# 3.net
KiCad netlist of a schematic drawn in Altium Designer
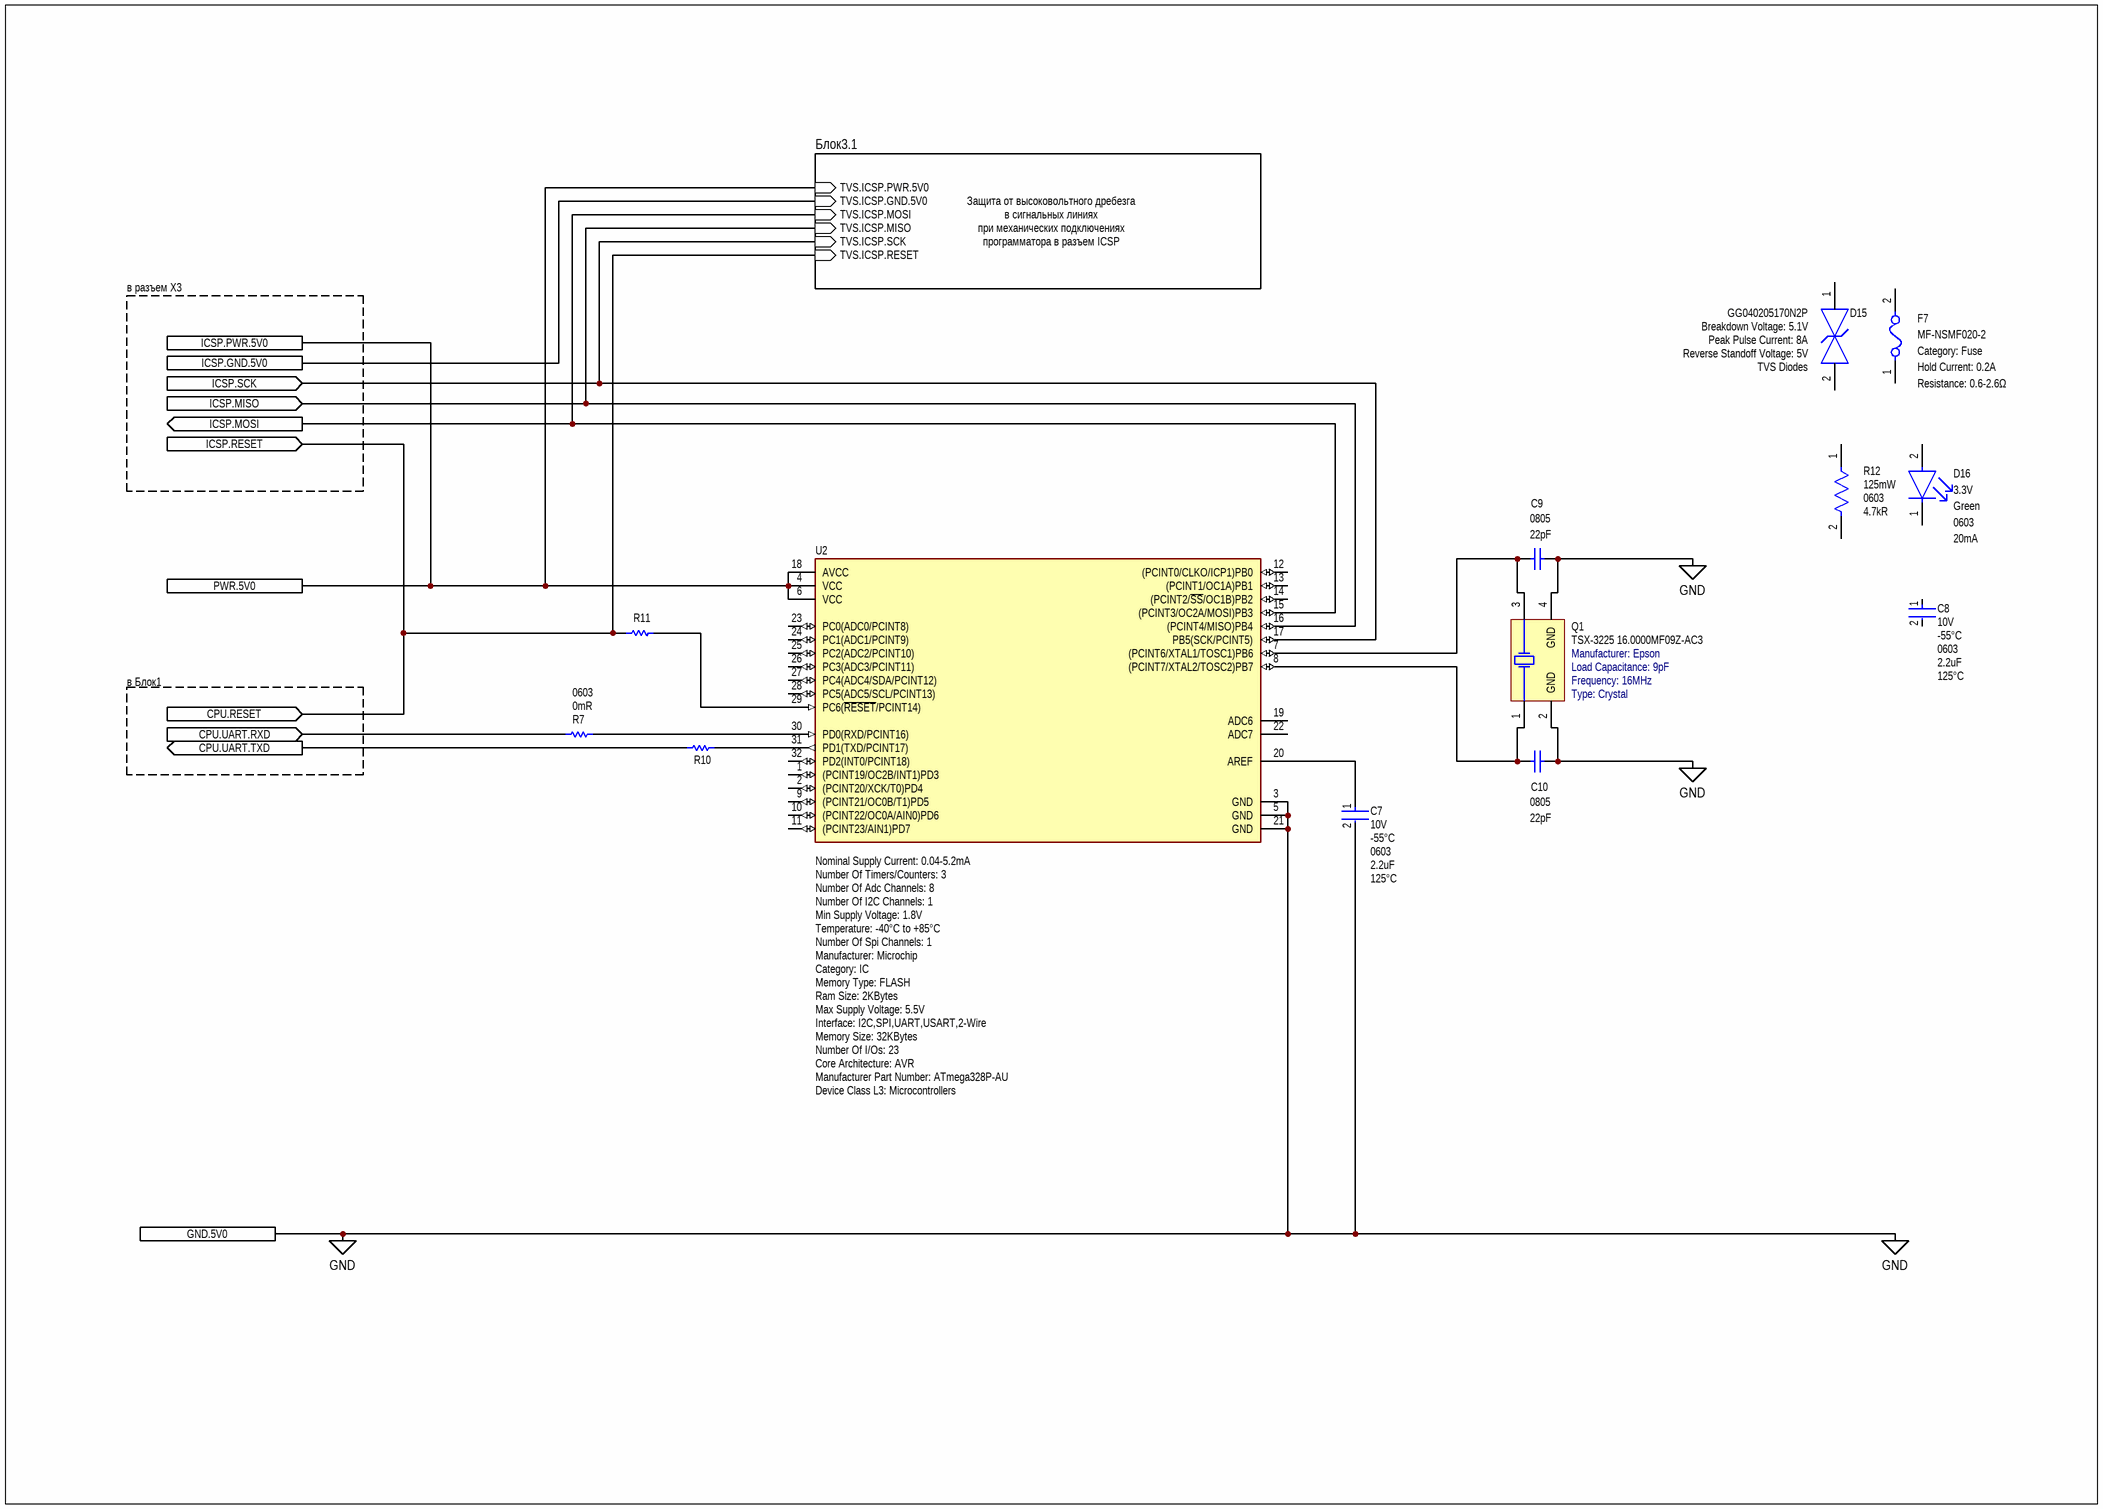
[diagram p0: Блок3.SchDoc]

(export (version "E")
  (design (tool "Eeschema 10.0.6"))
  (components
    (comp (ref "C7")
      (value "CL10B225KP8NFNC")
      (footprint "FP-CL10-IPC_A")
      (description "Cap Ceramic 2.2uF 10V X7R ±10% Pad SMD 0603 +125°C T/R")
      (fields
        (field (name "VOLTAGE RATING") "10V")
        (field (name "MIN OPERATING TEMPERATURE") "-55°C")
        (field (name "CASE CODE (IMPERIAL)") "0603")
        (field (name "CAPACITANCE") "2.2uF")
        (field (name "MAX OPERATING TEMPERATURE") "125°C")
        (field (name "TOLERANCE") "10%")
      )
      (libsource (lib "Altium Content Vault") (part "b4654b650e69147ec39a6b967a45e02"))
    )
    (comp (ref "C8")
      (value "CL10B225KP8NFNC")
      (footprint "FP-CL10-IPC_A")
      (description "Cap Ceramic 2.2uF 10V X7R ±10% Pad SMD 0603 +125°C T/R")
      (fields
        (field (name "VOLTAGE RATING") "10V")
        (field (name "MIN OPERATING TEMPERATURE") "-55°C")
        (field (name "CASE CODE (IMPERIAL)") "0603")
        (field (name "CAPACITANCE") "2.2uF")
        (field (name "MAX OPERATING TEMPERATURE") "125°C")
        (field (name "TOLERANCE") "10%")
      )
      (libsource (lib "Altium Content Vault") (part "b4654b650e69147ec39a6b967a45e02"))
    )
    (comp (ref "C9")
      (value "VJ0805A220GXXCW1BC")
      (footprint "CAPC2013X145X50ML20T20")
      (fields
        (field (name "MANUFACTURER") "Vitramon")
        (field (name "CASE/PACKAGE") "0805")
        (field (name "CAPACITANCE") "22pF")
        (field (name "TOLERANCE") "2%")
      )
      (libsource (lib "Altium Content Vault") (part "CAP"))
    )
    (comp (ref "C10")
      (value "VJ0805A220GXXCW1BC")
      (footprint "CAPC2013X145X50ML20T20")
      (fields
        (field (name "MANUFACTURER") "Vitramon")
        (field (name "CASE/PACKAGE") "0805")
        (field (name "CAPACITANCE") "22pF")
        (field (name "TOLERANCE") "2%")
      )
      (libsource (lib "Altium Content Vault") (part "CAP"))
    )
    (comp (ref "D15")
      (value "GG040205170N2P")
      (footprint "FP-GG0402-IPC_A")
      (description "TVS DIODE 5V 10V 0402")
      (fields
        (field (name "OCTOPART") "https://octopart.com/gg040205170n2p-avx-81066082")
        (field (name "MANUFACTURER") "AVX")
        (field (name "BREAKDOWN VOLTAGE") "5.1V")
        (field (name "PEAK PULSE CURRENT") "8A")
        (field (name "REVERSE STANDOFF VOLTAGE") "5V")
        (field (name "DEVICE CLASS L2") "TVS Diodes")
      )
      (libsource (lib "Altium Content Vault") (part "11bd9d59d340f0612179daf16ad9b72"))
    )
    (comp (ref "D16")
      (value "APT1608ZGCK")
      (footprint "FP-APT1608ZGCK-MFG")
      (description "LED GREEN CLEAR CHIP SMD")
      (fields
        (field (name "FORWARD VOLTAGE") "3.3V")
        (field (name "COLOR") "Green")
        (field (name "CASE/PACKAGE") "0603")
        (field (name "FORWARD CURRENT") "20mA")
      )
      (libsource (lib "Altium Content Vault") (part "8706943c75ba83719d021d2fdc84c58"))
    )
    (comp (ref "F7")
      (value "MF-NSMF020-2")
      (footprint "FP-MF-NSMF020-2-MFG")
      (description "PTC RESET FUSE 24V 200MA 1206")
      (fields
        (field (name "CATEGORY") "Fuse")
        (field (name "HOLD CURRENT") "0.2A")
        (field (name "MANUFACTURER") "Bourns")
        (field (name "OCTOPART") "https://octopart.com/mf-nsmf020-2-bourns-94649")
        (field (name "RESISTANCE") "0.6-2.6Ω")
      )
      (libsource (lib "Altium Content Vault") (part "5bcf9b9f640e542cf0359d10258e979"))
    )
    (comp (ref "Q1")
      (value "TSX-3225 16.0000MF09Z-AC3")
      (footprint "EPSON-TSX-3225_V")
      (description "Crystal, 16 MHz, -40 to 85 degC, 4-Pin SMD, RoHS, Tape and Reel")
      (fields
        (field (name "MANUFACTURER") "Epson")
        (field (name "LOAD CAPACITANCE") "9pF")
        (field (name "FREQUENCY") "16MHz")
        (field (name "TYPE") "Crystal")
        (field (name "TOLERANCE") "10PPM")
      )
      (libsource (lib "Altium Content Vault") (part "XTAL-1-3-4"))
    )
    (comp (ref "R7")
      (value "CRCW06030000Z0EA")
      (footprint "RESC1609X50X30NL8T20")
      (description "Chip Resistor, 0 Ohm, Jumper, 100 mW, -55 to 155 degC, 0603 (1608 Metric), RoHS, Tape and Reel")
      (fields
        (field (name "MANUFACTURER") "Vishay")
        (field (name "PACKAGEREFERENCE") "0603")
        (field (name "MANUFACTURER PART NUMBER") "CRCW0603-0000Z0EA")
        (field (name "RESISTANCE") "0mR")
      )
      (libsource (lib "Altium Content Vault") (part "RES-2"))
    )
    (comp (ref "R10")
      (value "CRCW06030000Z0EA")
      (footprint "RESC1609X50X30NL8T20")
      (description "Chip Resistor, 0 Ohm, Jumper, 100 mW, -55 to 155 degC, 0603 (1608 Metric), RoHS, Tape and Reel")
      (fields
        (field (name "MANUFACTURER") "Vishay")
        (field (name "MANUFACTURER PART NUMBER") "CRCW0603-0000Z0EA")
      )
      (libsource (lib "Altium Content Vault") (part "RES-2"))
    )
    (comp (ref "R11")
      (value "CRCW06030000Z0EA")
      (footprint "RESC1609X50X30NL8T20")
      (description "Chip Resistor, 0 Ohm, Jumper, 100 mW, -55 to 155 degC, 0603 (1608 Metric), RoHS, Tape and Reel")
      (fields
        (field (name "MANUFACTURER") "Vishay")
        (field (name "MANUFACTURER PART NUMBER") "CRCW0603-0000Z0EA")
      )
      (libsource (lib "Altium Content Vault") (part "RES-2"))
    )
    (comp (ref "R12")
      (value "MCT06030C4701FP500")
      (footprint "FP-MCT0603-MFG")
      (description "RES SMD 100 OHM 1% 1/8W 0603")
      (fields
        (field (name "POWER RATING") "125mW")
        (field (name "CASE/PACKAGE") "0603")
        (field (name "RESISTANCE") "4.7kR")
        (field (name "TOLERANCE") "1%")
      )
      (libsource (lib "Altium Content Vault") (part "1029c3af85768c4190bb7ad29bc67b5"))
    )
    (comp (ref "U2")
      (value "ATmega328P-AU")
      (footprint "FP-32A-IPC_A")
      (description "IC MCU 8BIT 32KB FLASH 32TQFP")
      (fields
        (field (name "NOMINAL SUPPLY CURRENT") "0.04-5.2mA")
        (field (name "NUMBER OF TIMERS/COUNTERS") "3")
        (field (name "NUMBER OF ADC CHANNELS") "8")
        (field (name "NUMBER OF I2C CHANNELS") "1")
        (field (name "MIN SUPPLY VOLTAGE") "1.8V")
        (field (name "TEMPERATURE") "-40°C to +85°C")
        (field (name "NUMBER OF SPI CHANNELS") "1")
        (field (name "MANUFACTURER") "Microchip")
        (field (name "CATEGORY") "IC")
        (field (name "MEMORY TYPE") "FLASH")
        (field (name "OCTOPART") "https://octopart.com/atmega328p-au-microchip-77760215")
        (field (name "RAM SIZE") "2KBytes")
        (field (name "MAX SUPPLY VOLTAGE") "5.5V")
        (field (name "INTERFACE") "I2C,SPI,UART,USART,2-Wire")
        (field (name "MEMORY SIZE") "32KBytes")
        (field (name "NUMBER OF I/OS") "23")
        (field (name "CORE ARCHITECTURE") "AVR")
        (field (name "MANUFACTURER PART NUMBER") "ATmega328P-AU")
        (field (name "DEVICE CLASS L3") "Microcontrollers")
      )
      (libsource (lib "Altium Content Vault") (part "f5fbdcb2c0c597ef7d3dd1575aef21a"))
    )
  )
  (nets
    (net (code "1") (name "/CPU.RESET") (class "Default")
      (node (ref "R11") (pin "1") (pinfunction "1_1") (pintype "passive"))
    )
    (net (code "2") (name "/CPU.UART.RXD") (class "Default")
      (node (ref "R7") (pin "1") (pinfunction "1_1") (pintype "passive"))
    )
    (net (code "3") (name "/CPU.UART.TXD") (class "Default")
      (node (ref "R10") (pin "1") (pinfunction "1_1") (pintype "passive"))
    )
    (net (code "5") (name "/ICSP.MISO") (class "Default")
      (node (ref "U2") (pin "16") (pinfunction "(PCINT4/MISO)PB4_16") (pintype "bidirectional"))
    )
    (net (code "6") (name "/ICSP.MOSI") (class "Default")
      (node (ref "U2") (pin "15") (pinfunction "(PCINT3/OC2A/MOSI)PB3_15") (pintype "bidirectional"))
    )
    (net (code "7") (name "/ICSP.PWR.5V0") (class "Default")
      (node (ref "U2") (pin "18") (pinfunction "AVCC_18") (pintype "power_in"))
      (node (ref "U2") (pin "4") (pinfunction "VCC_4") (pintype "power_in"))
      (node (ref "U2") (pin "6") (pinfunction "VCC_6") (pintype "power_in"))
    )
    (net (code "8") (name "/ICSP.SCK") (class "Default")
      (node (ref "U2") (pin "17") (pinfunction "PB5(SCK/PCINT5)_17") (pintype "bidirectional"))
    )
    (net (code "9") (name "GND") (class "Default")
      (node (ref "C10") (pin "2") (pinfunction "2_2") (pintype "passive"))
      (node (ref "C7") (pin "2") (pinfunction "2_2") (pintype "passive"))
      (node (ref "C9") (pin "2") (pinfunction "2_2") (pintype "passive"))
      (node (ref "Q1") (pin "2") (pinfunction "GND_2") (pintype "power_in"))
      (node (ref "Q1") (pin "4") (pinfunction "GND_4") (pintype "power_in"))
      (node (ref "U2") (pin "21") (pinfunction "GND_21") (pintype "power_in"))
      (node (ref "U2") (pin "3") (pinfunction "GND_3") (pintype "power_in"))
      (node (ref "U2") (pin "5") (pinfunction "GND_5") (pintype "power_in"))
    )
    (net (code "10") (name "Net-(Q1-X1)") (class "Default")
      (node (ref "C10") (pin "1") (pinfunction "1_1") (pintype "passive"))
      (node (ref "Q1") (pin "1") (pinfunction "X1_1") (pintype "passive"))
      (node (ref "U2") (pin "8") (pinfunction "(PCINT7/XTAL2/TOSC2)PB7_8") (pintype "bidirectional"))
    )
    (net (code "11") (name "Net-(Q1-X2)") (class "Default")
      (node (ref "C9") (pin "1") (pinfunction "1_1") (pintype "passive"))
      (node (ref "Q1") (pin "3") (pinfunction "X2_3") (pintype "passive"))
      (node (ref "U2") (pin "7") (pinfunction "(PCINT6/XTAL1/TOSC1)PB6_7") (pintype "bidirectional"))
    )
    (net (code "12") (name "Net-(U2-AREF)") (class "Default")
      (node (ref "C7") (pin "1") (pinfunction "1_1") (pintype "passive"))
      (node (ref "U2") (pin "20") (pinfunction "AREF_20") (pintype "passive"))
    )
    (net (code "13") (name "Net-(U2-PC6(~{RESET}{slash}PCINT14))") (class "Default")
      (node (ref "R11") (pin "2") (pinfunction "2_2") (pintype "passive"))
      (node (ref "U2") (pin "29") (pinfunction "PC6(~{RESET}/PCINT14)_29") (pintype "input"))
    )
    (net (code "14") (name "Net-(U2-PD0(RXD{slash}PCINT16))") (class "Default")
      (node (ref "R7") (pin "2") (pinfunction "2_2") (pintype "passive"))
      (node (ref "U2") (pin "30") (pinfunction "PD0(RXD/PCINT16)_30") (pintype "input"))
    )
    (net (code "15") (name "Net-(U2-PD1(TXD{slash}PCINT17))") (class "Default")
      (node (ref "R10") (pin "2") (pinfunction "2_2") (pintype "passive"))
      (node (ref "U2") (pin "31") (pinfunction "PD1(TXD/PCINT17)_31") (pintype "output"))
    )
    (net (code "16") (name "unconnected-(C8-Pad1)") (class "Default")
      (node (ref "C8") (pin "1") (pinfunction "1_1") (pintype "passive"))
    )
    (net (code "17") (name "unconnected-(C8-Pad2)") (class "Default")
      (node (ref "C8") (pin "2") (pinfunction "2_2") (pintype "passive"))
    )
    (net (code "18") (name "unconnected-(D15-Pad1)") (class "Default")
      (node (ref "D15") (pin "1") (pinfunction "1_1") (pintype "passive"))
    )
    (net (code "19") (name "unconnected-(D15-Pad2)") (class "Default")
      (node (ref "D15") (pin "2") (pinfunction "2_2") (pintype "passive"))
    )
    (net (code "20") (name "unconnected-(D16-A-Pad2)") (class "Default")
      (node (ref "D16") (pin "2") (pinfunction "A_2") (pintype "passive"))
    )
    (net (code "21") (name "unconnected-(D16-C-Pad1)") (class "Default")
      (node (ref "D16") (pin "1") (pinfunction "C_1") (pintype "passive"))
    )
    (net (code "22") (name "unconnected-(F7-Pad1)") (class "Default")
      (node (ref "F7") (pin "1") (pinfunction "1_1") (pintype "passive"))
    )
    (net (code "23") (name "unconnected-(F7-Pad2)") (class "Default")
      (node (ref "F7") (pin "2") (pinfunction "2_2") (pintype "passive"))
    )
    (net (code "24") (name "unconnected-(R12-Pad1)") (class "Default")
      (node (ref "R12") (pin "1") (pinfunction "1_1") (pintype "passive"))
    )
    (net (code "25") (name "unconnected-(R12-Pad2)") (class "Default")
      (node (ref "R12") (pin "2") (pinfunction "2_2") (pintype "passive"))
    )
    (net (code "26") (name "unconnected-(U2-(PCINT0{slash}CLKO{slash}ICP1)PB0-Pad12)") (class "Default")
      (node (ref "U2") (pin "12") (pinfunction "(PCINT0/CLKO/ICP1)PB0_12") (pintype "bidirectional"))
    )
    (net (code "27") (name "unconnected-(U2-(PCINT1{slash}OC1A)PB1-Pad13)") (class "Default")
      (node (ref "U2") (pin "13") (pinfunction "(PCINT1/OC1A)PB1_13") (pintype "bidirectional"))
    )
    (net (code "28") (name "unconnected-(U2-(PCINT2{slash}~{SS}{slash}OC1B)PB2-Pad14)") (class "Default")
      (node (ref "U2") (pin "14") (pinfunction "(PCINT2/~{SS}/OC1B)PB2_14") (pintype "bidirectional"))
    )
    (net (code "29") (name "unconnected-(U2-(PCINT19{slash}OC2B{slash}INT1)PD3-Pad1)") (class "Default")
      (node (ref "U2") (pin "1") (pinfunction "(PCINT19/OC2B/INT1)PD3_1") (pintype "bidirectional"))
    )
    (net (code "30") (name "unconnected-(U2-(PCINT20{slash}XCK{slash}T0)PD4-Pad2)") (class "Default")
      (node (ref "U2") (pin "2") (pinfunction "(PCINT20/XCK/T0)PD4_2") (pintype "bidirectional"))
    )
    (net (code "31") (name "unconnected-(U2-(PCINT21{slash}OC0B{slash}T1)PD5-Pad9)") (class "Default")
      (node (ref "U2") (pin "9") (pinfunction "(PCINT21/OC0B/T1)PD5_9") (pintype "bidirectional"))
    )
    (net (code "32") (name "unconnected-(U2-(PCINT22{slash}OC0A{slash}AIN0)PD6-Pad10)") (class "Default")
      (node (ref "U2") (pin "10") (pinfunction "(PCINT22/OC0A/AIN0)PD6_10") (pintype "bidirectional"))
    )
    (net (code "33") (name "unconnected-(U2-(PCINT23{slash}AIN1)PD7-Pad11)") (class "Default")
      (node (ref "U2") (pin "11") (pinfunction "(PCINT23/AIN1)PD7_11") (pintype "bidirectional"))
    )
    (net (code "34") (name "unconnected-(U2-ADC6-Pad19)") (class "Default")
      (node (ref "U2") (pin "19") (pinfunction "ADC6_19") (pintype "power_in"))
    )
    (net (code "35") (name "unconnected-(U2-ADC7-Pad22)") (class "Default")
      (node (ref "U2") (pin "22") (pinfunction "ADC7_22") (pintype "passive"))
    )
    (net (code "36") (name "unconnected-(U2-PC0(ADC0{slash}PCINT8)-Pad23)") (class "Default")
      (node (ref "U2") (pin "23") (pinfunction "PC0(ADC0/PCINT8)_23") (pintype "bidirectional"))
    )
    (net (code "37") (name "unconnected-(U2-PC1(ADC1{slash}PCINT9)-Pad24)") (class "Default")
      (node (ref "U2") (pin "24") (pinfunction "PC1(ADC1/PCINT9)_24") (pintype "bidirectional"))
    )
    (net (code "38") (name "unconnected-(U2-PC2(ADC2{slash}PCINT10)-Pad25)") (class "Default")
      (node (ref "U2") (pin "25") (pinfunction "PC2(ADC2/PCINT10)_25") (pintype "bidirectional"))
    )
    (net (code "39") (name "unconnected-(U2-PC3(ADC3{slash}PCINT11)-Pad26)") (class "Default")
      (node (ref "U2") (pin "26") (pinfunction "PC3(ADC3/PCINT11)_26") (pintype "bidirectional"))
    )
    (net (code "40") (name "unconnected-(U2-PC4(ADC4{slash}SDA{slash}PCINT12)-Pad27)") (class "Default")
      (node (ref "U2") (pin "27") (pinfunction "PC4(ADC4/SDA/PCINT12)_27") (pintype "bidirectional"))
    )
    (net (code "41") (name "unconnected-(U2-PC5(ADC5{slash}SCL{slash}PCINT13)-Pad28)") (class "Default")
      (node (ref "U2") (pin "28") (pinfunction "PC5(ADC5/SCL/PCINT13)_28") (pintype "bidirectional"))
    )
    (net (code "42") (name "unconnected-(U2-PD2(INT0{slash}PCINT18)-Pad32)") (class "Default")
      (node (ref "U2") (pin "32") (pinfunction "PD2(INT0/PCINT18)_32") (pintype "bidirectional"))
    )
  )
)
